# MySLipo_v1_0.net
KiCad netlist of a schematic drawn in EAGLE
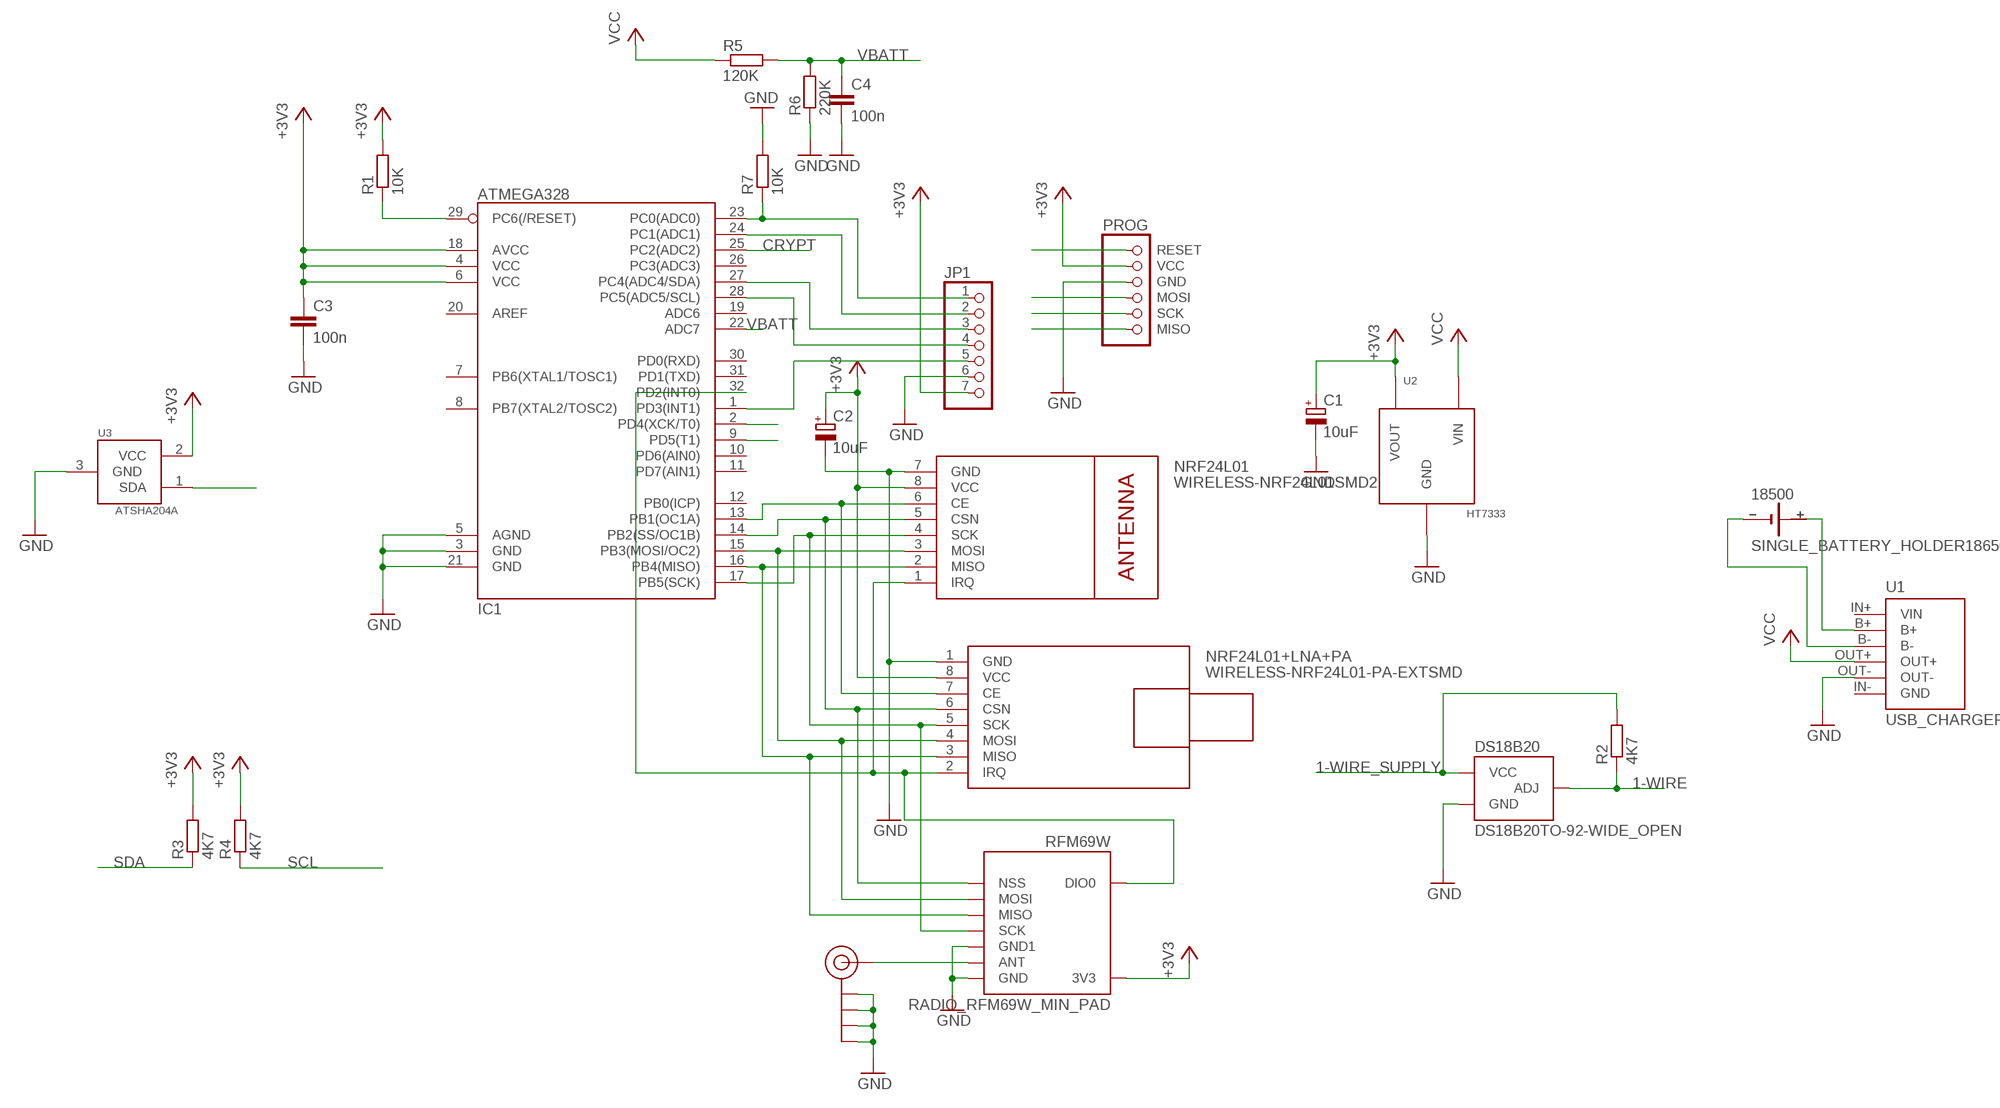
[diagram p0: schematic, sheet 1]

(export (version "E")
  (design (tool "Eeschema 10.0.6"))
  (components
    (comp (ref "18500")
      (value "SINGLE_BATTERY_HOLDER18650")
      (footprint "eagle-import:18650_HOLDER")
      (libsource (lib "eagle-import") (part "SINGLE_BATTERY_HOLDER18650"))
    )
    (comp (ref "C1")
      (value "10uF")
      (footprint "eagle-import:SMC_A")
      (libsource (lib "eagle-import") (part "CPOL-EUSMCA"))
    )
    (comp (ref "C2")
      (value "10uF")
      (footprint "eagle-import:SMC_A")
      (libsource (lib "eagle-import") (part "CPOL-EUSMCA"))
    )
    (comp (ref "C3")
      (value "100n")
      (footprint "eagle-import:C0805")
      (libsource (lib "eagle-import") (part "C-EUC0805"))
    )
    (comp (ref "C4")
      (value "100n")
      (footprint "eagle-import:C0805")
      (libsource (lib "eagle-import") (part "C-EUC0805"))
    )
    (comp (ref "DS18B20")
      (value "DS18B20TO-92-WIDE_OPEN")
      (footprint "eagle-import:TO-92-WIDE_OPEN")
      (libsource (lib "eagle-import") (part "DS18B20TO-92-WIDE_OPEN"))
    )
    (comp (ref "IC1")
      (value "ATMEGA328")
      (footprint "eagle-import:TQFP32-08")
      (libsource (lib "eagle-import") (part "ATMEGA328"))
    )
    (comp (ref "J$1")
      (value "ANTENNATINY")
      (footprint "eagle-import:SMA_UFL_PAD_TINY")
      (libsource (lib "eagle-import") (part "ANTENNATINY"))
    )
    (comp (ref "JP1")
      (value "PINHD-1X7")
      (footprint "eagle-import:1X07")
      (libsource (lib "eagle-import") (part "PINHD-1X7"))
    )
    (comp (ref "NRF24L01")
      (value "WIRELESS-NRF24L01SMD2")
      (footprint "eagle-import:WIRELESS-NRF24L01-SMD-2")
      (libsource (lib "eagle-import") (part "WIRELESS-NRF24L01SMD2"))
    )
    (comp (ref "NRF24L01+LNA+PA")
      (value "WIRELESS-NRF24L01-PA-EXTSMD")
      (footprint "eagle-import:WIRELESS-NRF24L01-PA-SMD")
      (libsource (lib "eagle-import") (part "WIRELESS-NRF24L01-PA-EXTSMD"))
    )
    (comp (ref "PROG")
      (value "PROG")
      (footprint "eagle-import:PROG")
      (libsource (lib "eagle-import") (part "PROG"))
    )
    (comp (ref "R1")
      (value "10K")
      (footprint "eagle-import:R0805")
      (libsource (lib "eagle-import") (part "R-EU_R0805"))
    )
    (comp (ref "R2")
      (value "4K7")
      (footprint "eagle-import:R0805")
      (libsource (lib "eagle-import") (part "R-EU_R0805"))
    )
    (comp (ref "R3")
      (value "4K7")
      (footprint "eagle-import:R0805")
      (libsource (lib "eagle-import") (part "R-EU_R0805"))
    )
    (comp (ref "R4")
      (value "4K7")
      (footprint "eagle-import:R0805")
      (libsource (lib "eagle-import") (part "R-EU_R0805"))
    )
    (comp (ref "R5")
      (value "120K")
      (footprint "eagle-import:R0805")
      (libsource (lib "eagle-import") (part "R-EU_R0805"))
    )
    (comp (ref "R6")
      (value "220K")
      (footprint "eagle-import:R0805")
      (libsource (lib "eagle-import") (part "R-EU_R0805"))
    )
    (comp (ref "R7")
      (value "10K")
      (footprint "eagle-import:R0805")
      (libsource (lib "eagle-import") (part "R-EU_R0805"))
    )
    (comp (ref "RFM69W")
      (value "RADIO_RFM69W_MIN_PAD")
      (footprint "eagle-import:RFM69W_MIN_PAD")
      (libsource (lib "eagle-import") (part "RADIO_RFM69W_MIN_PAD"))
    )
    (comp (ref "U1")
      (value "USB_CHARGER")
      (footprint "eagle-import:USB_CHARGER")
      (libsource (lib "eagle-import") (part "USB_CHARGER"))
    )
    (comp (ref "U2")
      (value "HT7333")
      (footprint "eagle-import:SOT-89")
      (libsource (lib "eagle-import") (part "HT73XX"))
    )
    (comp (ref "U3")
      (value "ATSHA204A")
      (footprint "eagle-import:SOT23-3")
      (libsource (lib "eagle-import") (part "IC_ATSHA204A_CRYPT"))
    )
  )
  (nets
    (net (code "1") (name "+3V3") (class "Default")
      (node (ref "C1") (pin "+") (pinfunction "+_+") (pintype "passive"))
      (node (ref "C2") (pin "+") (pinfunction "+_+") (pintype "passive"))
      (node (ref "C3") (pin "1") (pinfunction "1_1") (pintype "passive"))
      (node (ref "IC1") (pin "18") (pinfunction "AVCC_18") (pintype "bidirectional"))
      (node (ref "IC1") (pin "4") (pinfunction "VCC_4") (pintype "bidirectional"))
      (node (ref "IC1") (pin "6") (pinfunction "VCC_6") (pintype "bidirectional"))
      (node (ref "JP1") (pin "7") (pinfunction "7_7") (pintype "passive"))
      (node (ref "NRF24L01") (pin "8") (pinfunction "VCC_8") (pintype "power_in"))
      (node (ref "NRF24L01+LNA+PA") (pin "8") (pinfunction "VCC_8") (pintype "power_in"))
      (node (ref "PROG") (pin "2") (pinfunction "VCC_2") (pintype "passive"))
      (node (ref "R1") (pin "2") (pinfunction "2_2") (pintype "passive"))
      (node (ref "R3") (pin "2") (pinfunction "2_2") (pintype "passive"))
      (node (ref "R4") (pin "2") (pinfunction "2_2") (pintype "passive"))
      (node (ref "RFM69W") (pin "8") (pinfunction "3V3_8") (pintype "power_in"))
      (node (ref "U2") (pin "3") (pinfunction "VOUT_3") (pintype "power_in"))
      (node (ref "U3") (pin "2") (pinfunction "VCC_2") (pintype "bidirectional"))
    )
    (net (code "2") (name "/1-WIRE") (class "Default")
      (node (ref "DS18B20") (pin "G") (pinfunction "ADJ_G") (pintype "output"))
      (node (ref "IC1") (pin "2") (pinfunction "PD4(XCK/T0)_2") (pintype "bidirectional"))
      (node (ref "R2") (pin "1") (pinfunction "1_1") (pintype "passive"))
    )
    (net (code "3") (name "/1-WIRE_SUPPLY") (class "Default")
      (node (ref "DS18B20") (pin "D") (pinfunction "VCC_D") (pintype "passive"))
      (node (ref "IC1") (pin "9") (pinfunction "PD5(T1)_9") (pintype "bidirectional"))
      (node (ref "R2") (pin "2") (pinfunction "2_2") (pintype "passive"))
    )
    (net (code "4") (name "/CRYPT") (class "Default")
      (node (ref "IC1") (pin "25") (pinfunction "PC2(ADC2)_25") (pintype "bidirectional"))
      (node (ref "U3") (pin "1") (pinfunction "SDA_1") (pintype "bidirectional"))
    )
    (net (code "5") (name "/MISO") (class "Default")
      (node (ref "IC1") (pin "16") (pinfunction "PB4(MISO)_16") (pintype "bidirectional"))
      (node (ref "NRF24L01") (pin "2") (pinfunction "MISO_2") (pintype "bidirectional"))
      (node (ref "NRF24L01+LNA+PA") (pin "3") (pinfunction "MISO_3") (pintype "bidirectional"))
      (node (ref "PROG") (pin "6") (pinfunction "MISO_6") (pintype "passive"))
      (node (ref "RFM69W") (pin "13") (pinfunction "MISO_13") (pintype "bidirectional"))
    )
    (net (code "6") (name "/MOSI") (class "Default")
      (node (ref "IC1") (pin "15") (pinfunction "PB3(MOSI/OC2)_15") (pintype "bidirectional"))
      (node (ref "NRF24L01") (pin "3") (pinfunction "MOSI_3") (pintype "bidirectional"))
      (node (ref "NRF24L01+LNA+PA") (pin "4") (pinfunction "MOSI_4") (pintype "bidirectional"))
      (node (ref "PROG") (pin "4") (pinfunction "MOSI_4") (pintype "passive"))
      (node (ref "RFM69W") (pin "14") (pinfunction "MOSI_14") (pintype "bidirectional"))
    )
    (net (code "7") (name "/RESET") (class "Default")
      (node (ref "IC1") (pin "29") (pinfunction "PC6(/RESET)_29") (pintype "bidirectional"))
      (node (ref "PROG") (pin "1") (pinfunction "RESET_1") (pintype "passive"))
      (node (ref "R1") (pin "1") (pinfunction "1_1") (pintype "passive"))
    )
    (net (code "8") (name "/SCK") (class "Default")
      (node (ref "IC1") (pin "17") (pinfunction "PB5(SCK)_17") (pintype "bidirectional"))
      (node (ref "NRF24L01") (pin "4") (pinfunction "SCK_4") (pintype "bidirectional"))
      (node (ref "NRF24L01+LNA+PA") (pin "5") (pinfunction "SCK_5") (pintype "bidirectional"))
      (node (ref "PROG") (pin "5") (pinfunction "SCK_5") (pintype "passive"))
      (node (ref "RFM69W") (pin "12") (pinfunction "SCK_12") (pintype "bidirectional"))
    )
    (net (code "9") (name "/SCL") (class "Default")
      (node (ref "IC1") (pin "28") (pinfunction "PC5(ADC5/SCL)_28") (pintype "bidirectional"))
      (node (ref "JP1") (pin "4") (pinfunction "4_4") (pintype "passive"))
      (node (ref "R4") (pin "1") (pinfunction "1_1") (pintype "passive"))
    )
    (net (code "10") (name "/SDA") (class "Default")
      (node (ref "IC1") (pin "27") (pinfunction "PC4(ADC4/SDA)_27") (pintype "bidirectional"))
      (node (ref "JP1") (pin "3") (pinfunction "3_3") (pintype "passive"))
      (node (ref "R3") (pin "1") (pinfunction "1_1") (pintype "passive"))
    )
    (net (code "11") (name "/VBATT") (class "Default")
      (node (ref "C4") (pin "1") (pinfunction "1_1") (pintype "passive"))
      (node (ref "IC1") (pin "22") (pinfunction "ADC7_22") (pintype "bidirectional"))
      (node (ref "R5") (pin "2") (pinfunction "2_2") (pintype "passive"))
      (node (ref "R6") (pin "2") (pinfunction "2_2") (pintype "passive"))
    )
    (net (code "12") (name "GND") (class "Default")
      (node (ref "C1") (pin "-") (pinfunction "-_-") (pintype "passive"))
      (node (ref "C2") (pin "-") (pinfunction "-_-") (pintype "passive"))
      (node (ref "C3") (pin "2") (pinfunction "2_2") (pintype "passive"))
      (node (ref "C4") (pin "2") (pinfunction "2_2") (pintype "passive"))
      (node (ref "DS18B20") (pin "S") (pinfunction "GND_S") (pintype "power_in"))
      (node (ref "IC1") (pin "21") (pinfunction "GND_21") (pintype "bidirectional"))
      (node (ref "IC1") (pin "3") (pinfunction "GND_3") (pintype "bidirectional"))
      (node (ref "IC1") (pin "5") (pinfunction "AGND_5") (pintype "bidirectional"))
      (node (ref "J$1") (pin "GND1") (pinfunction "GND_GND1") (pintype "bidirectional"))
      (node (ref "J$1") (pin "GND2") (pinfunction "GND_GND2") (pintype "bidirectional"))
      (node (ref "J$1") (pin "GND3") (pinfunction "GND_GND3") (pintype "bidirectional"))
      (node (ref "J$1") (pin "GND4") (pinfunction "GND_GND4") (pintype "bidirectional"))
      (node (ref "JP1") (pin "6") (pinfunction "6_6") (pintype "passive"))
      (node (ref "NRF24L01") (pin "7") (pinfunction "GND_7") (pintype "power_in"))
      (node (ref "NRF24L01+LNA+PA") (pin "1") (pinfunction "GND_1") (pintype "power_in"))
      (node (ref "PROG") (pin "3") (pinfunction "GND_3") (pintype "passive"))
      (node (ref "R6") (pin "1") (pinfunction "1_1") (pintype "passive"))
      (node (ref "R7") (pin "2") (pinfunction "2_2") (pintype "passive"))
      (node (ref "RFM69W") (pin "11") (pinfunction "GND1_11") (pintype "power_in"))
      (node (ref "RFM69W") (pin "9") (pinfunction "GND_9") (pintype "power_in"))
      (node (ref "U1") (pin "OUT-") (pinfunction "OUT-_OUT-") (pintype "bidirectional"))
      (node (ref "U2") (pin "1") (pinfunction "GND_1") (pintype "power_in"))
      (node (ref "U3") (pin "3") (pinfunction "GND_3") (pintype "bidirectional"))
    )
    (net (code "13") (name "Net-(18500-Pad+)") (class "Default")
      (node (ref "18500") (pin "+") (pinfunction "+_+") (pintype "passive"))
      (node (ref "U1") (pin "B+") (pinfunction "B+_B+") (pintype "bidirectional"))
    )
    (net (code "14") (name "Net-(18500-Pad-)") (class "Default")
      (node (ref "18500") (pin "-") (pinfunction "-_-") (pintype "passive"))
      (node (ref "U1") (pin "B-") (pinfunction "B-_B-") (pintype "bidirectional"))
    )
    (net (code "15") (name "Net-(IC1-PB1(OC1A))") (class "Default")
      (node (ref "IC1") (pin "13") (pinfunction "PB1(OC1A)_13") (pintype "bidirectional"))
      (node (ref "NRF24L01") (pin "6") (pinfunction "CE_6") (pintype "bidirectional"))
      (node (ref "NRF24L01+LNA+PA") (pin "7") (pinfunction "CE_7") (pintype "bidirectional"))
    )
    (net (code "16") (name "Net-(IC1-PB2(SS{slash}OC1B))") (class "Default")
      (node (ref "IC1") (pin "14") (pinfunction "PB2(SS/OC1B)_14") (pintype "bidirectional"))
      (node (ref "NRF24L01") (pin "5") (pinfunction "CSN_5") (pintype "bidirectional"))
      (node (ref "NRF24L01+LNA+PA") (pin "6") (pinfunction "CSN_6") (pintype "bidirectional"))
      (node (ref "RFM69W") (pin "15") (pinfunction "NSS_15") (pintype "bidirectional"))
    )
    (net (code "17") (name "Net-(IC1-PC0(ADC0))") (class "Default")
      (node (ref "IC1") (pin "23") (pinfunction "PC0(ADC0)_23") (pintype "bidirectional"))
      (node (ref "JP1") (pin "1") (pinfunction "1_1") (pintype "passive"))
      (node (ref "R7") (pin "1") (pinfunction "1_1") (pintype "passive"))
    )
    (net (code "18") (name "Net-(IC1-PC1(ADC1))") (class "Default")
      (node (ref "IC1") (pin "24") (pinfunction "PC1(ADC1)_24") (pintype "bidirectional"))
      (node (ref "JP1") (pin "2") (pinfunction "2_2") (pintype "passive"))
    )
    (net (code "19") (name "Net-(IC1-PD2(INT0))") (class "Default")
      (node (ref "IC1") (pin "32") (pinfunction "PD2(INT0)_32") (pintype "bidirectional"))
      (node (ref "NRF24L01") (pin "1") (pinfunction "IRQ_1") (pintype "bidirectional"))
      (node (ref "NRF24L01+LNA+PA") (pin "2") (pinfunction "IRQ_2") (pintype "bidirectional"))
      (node (ref "RFM69W") (pin "2") (pinfunction "DIO0_2") (pintype "bidirectional"))
    )
    (net (code "20") (name "Net-(IC1-PD3(INT1))") (class "Default")
      (node (ref "IC1") (pin "1") (pinfunction "PD3(INT1)_1") (pintype "bidirectional"))
      (node (ref "JP1") (pin "5") (pinfunction "5_5") (pintype "passive"))
    )
    (net (code "21") (name "Net-(RFM69W-ANT)") (class "Default")
      (node (ref "J$1") (pin "ANT1") (pinfunction "SIGNAL_ANT1") (pintype "bidirectional"))
      (node (ref "J$1") (pin "ANT2") (pinfunction "SIGNAL_ANT2") (pintype "bidirectional"))
      (node (ref "J$1") (pin "ANT3") (pinfunction "SIGNAL_ANT3") (pintype "bidirectional"))
      (node (ref "RFM69W") (pin "10") (pinfunction "ANT_10") (pintype "bidirectional"))
    )
    (net (code "22") (name "VCC") (class "Default")
      (node (ref "R5") (pin "1") (pinfunction "1_1") (pintype "passive"))
      (node (ref "U1") (pin "OUT+") (pinfunction "OUT+_OUT+") (pintype "bidirectional"))
      (node (ref "U2") (pin "2") (pinfunction "VIN_2") (pintype "power_in"))
      (node (ref "U2") (pin "2@1") (pinfunction "VIN_2@1") (pintype "power_in"))
    )
    (net (code "23") (name "unconnected-(IC1-ADC6-Pad19)") (class "Default")
      (node (ref "IC1") (pin "19") (pinfunction "ADC6_19") (pintype "bidirectional"))
    )
    (net (code "24") (name "unconnected-(IC1-AREF-Pad20)") (class "Default")
      (node (ref "IC1") (pin "20") (pinfunction "AREF_20") (pintype "bidirectional"))
    )
    (net (code "25") (name "unconnected-(IC1-PB0(ICP)-Pad12)") (class "Default")
      (node (ref "IC1") (pin "12") (pinfunction "PB0(ICP)_12") (pintype "bidirectional"))
    )
    (net (code "26") (name "unconnected-(IC1-PB6(XTAL1{slash}TOSC1)-Pad7)") (class "Default")
      (node (ref "IC1") (pin "7") (pinfunction "PB6(XTAL1/TOSC1)_7") (pintype "bidirectional"))
    )
    (net (code "27") (name "unconnected-(IC1-PB7(XTAL2{slash}TOSC2)-Pad8)") (class "Default")
      (node (ref "IC1") (pin "8") (pinfunction "PB7(XTAL2/TOSC2)_8") (pintype "bidirectional"))
    )
    (net (code "28") (name "unconnected-(IC1-PC3(ADC3)-Pad26)") (class "Default")
      (node (ref "IC1") (pin "26") (pinfunction "PC3(ADC3)_26") (pintype "bidirectional"))
    )
    (net (code "29") (name "unconnected-(IC1-PD0(RXD)-Pad30)") (class "Default")
      (node (ref "IC1") (pin "30") (pinfunction "PD0(RXD)_30") (pintype "bidirectional"))
    )
    (net (code "30") (name "unconnected-(IC1-PD1(TXD)-Pad31)") (class "Default")
      (node (ref "IC1") (pin "31") (pinfunction "PD1(TXD)_31") (pintype "bidirectional"))
    )
    (net (code "31") (name "unconnected-(IC1-PD6(AIN0)-Pad10)") (class "Default")
      (node (ref "IC1") (pin "10") (pinfunction "PD6(AIN0)_10") (pintype "bidirectional"))
    )
    (net (code "32") (name "unconnected-(IC1-PD7(AIN1)-Pad11)") (class "Default")
      (node (ref "IC1") (pin "11") (pinfunction "PD7(AIN1)_11") (pintype "bidirectional"))
    )
    (net (code "33") (name "unconnected-(U1-GND-PadIN-)") (class "Default")
      (node (ref "U1") (pin "IN-") (pinfunction "GND_IN-") (pintype "bidirectional"))
    )
    (net (code "34") (name "unconnected-(U1-VIN-PadIN+)") (class "Default")
      (node (ref "U1") (pin "IN+") (pinfunction "VIN_IN+") (pintype "bidirectional"))
    )
  )
)
